# SparkFun_Main_Board_Single_v21.net
KiCad netlist of a schematic drawn in EAGLE
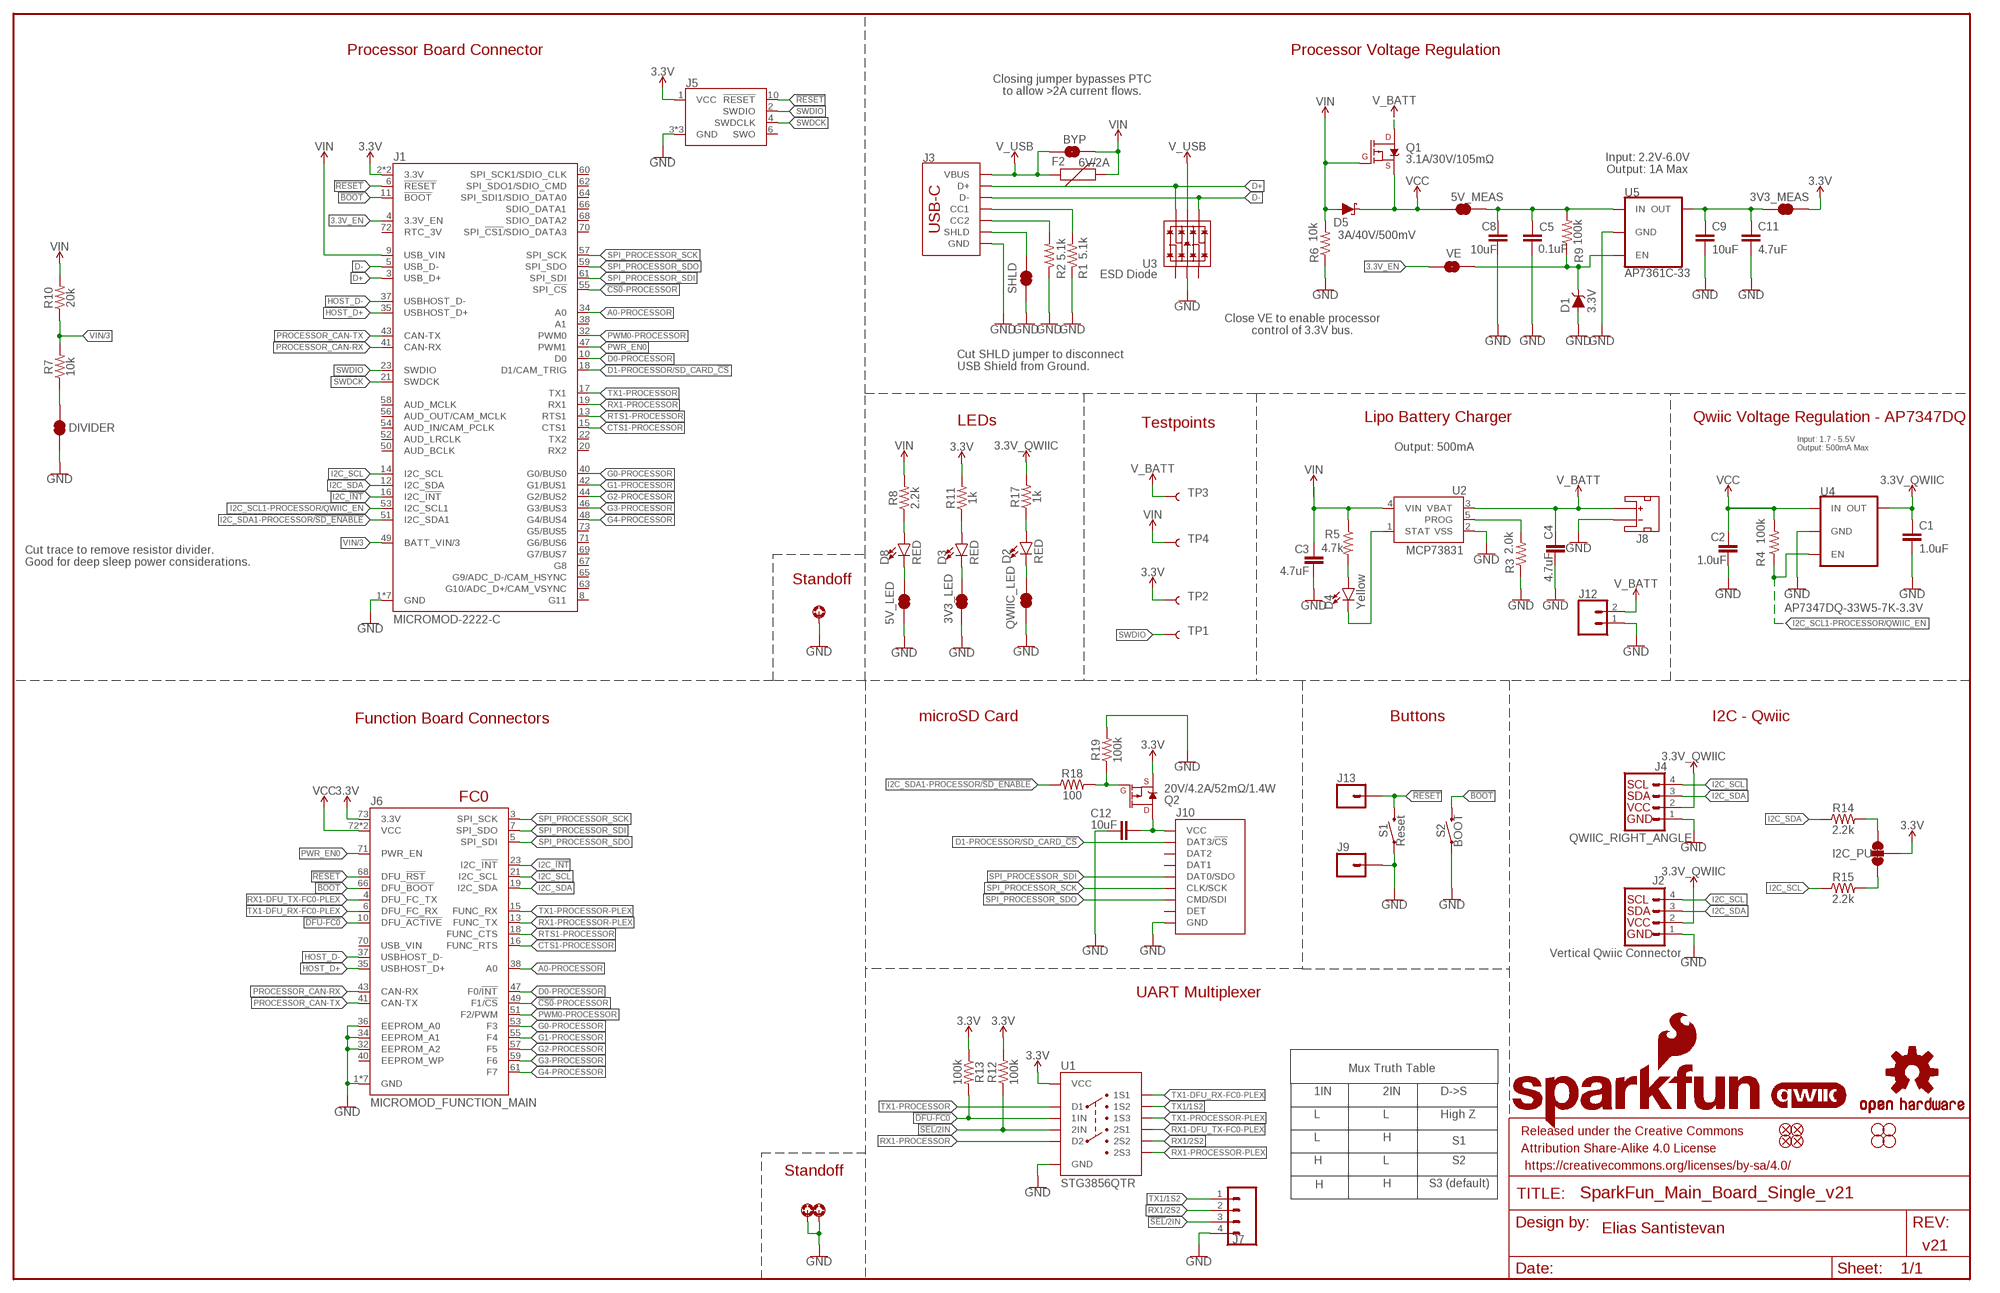
[diagram p0: schematic, sheet 1]

(export (version "E")
  (design (tool "Eeschema 10.0.6"))
  (components
    (comp (ref "3V3_LED")
      (value "JUMPER-SMT_2_NC_TRACE_SILK")
      (footprint "eagle-import:SMT-JUMPER_2_NC_TRACE_SILK")
      (libsource (lib "eagle-import") (part "JUMPER-SMT_2_NC_TRACE_SILK"))
    )
    (comp (ref "3V3_MEAS")
      (value "JUMPER-COMBO_2_NC_TRACE")
      (footprint "eagle-import:COMBO-JUMPER_2_NC_TRACE")
      (libsource (lib "eagle-import") (part "JUMPER-COMBO_2_NC_TRACE"))
    )
    (comp (ref "5V_LED")
      (value "JUMPER-SMT_2_NC_TRACE_SILK")
      (footprint "eagle-import:SMT-JUMPER_2_NC_TRACE_SILK")
      (libsource (lib "eagle-import") (part "JUMPER-SMT_2_NC_TRACE_SILK"))
    )
    (comp (ref "5V_MEAS")
      (value "JUMPER-COMBO_2_NC_TRACE")
      (footprint "eagle-import:COMBO-JUMPER_2_NC_TRACE")
      (libsource (lib "eagle-import") (part "JUMPER-COMBO_2_NC_TRACE"))
    )
    (comp (ref "BYP")
      (value "JUMPER-SMT_2_NO_SILK")
      (footprint "eagle-import:SMT-JUMPER_2_NO_SILK")
      (libsource (lib "eagle-import") (part "JUMPER-SMT_2_NO_SILK"))
    )
    (comp (ref "C1")
      (value "1.0uF")
      (footprint "eagle-import:0603")
      (libsource (lib "eagle-import") (part "1.0UF-0603-16V-10%"))
    )
    (comp (ref "C2")
      (value "1.0uF")
      (footprint "eagle-import:0603")
      (libsource (lib "eagle-import") (part "1.0UF-0603-16V-10%"))
    )
    (comp (ref "C3")
      (value "4.7uF")
      (footprint "eagle-import:0603")
      (libsource (lib "eagle-import") (part "4.7UF-0603-6.3V-(10%)"))
    )
    (comp (ref "C4")
      (value "4.7uF")
      (footprint "eagle-import:0603")
      (libsource (lib "eagle-import") (part "4.7UF-0603-35V-(20%)"))
    )
    (comp (ref "C5")
      (value "0.1uF")
      (footprint "eagle-import:0603")
      (libsource (lib "eagle-import") (part "0.1UF-0603-25V-(+80/-20%)"))
    )
    (comp (ref "C8")
      (value "10uF")
      (footprint "eagle-import:0805")
      (libsource (lib "eagle-import") (part "10UF-0805-10V-10%"))
    )
    (comp (ref "C9")
      (value "10uF")
      (footprint "eagle-import:0603")
      (libsource (lib "eagle-import") (part "10UF-0603-6.3V-20%"))
    )
    (comp (ref "C11")
      (value "4.7uF")
      (footprint "eagle-import:0603")
      (libsource (lib "eagle-import") (part "4.7UF-0603-6.3V-(10%)"))
    )
    (comp (ref "C12")
      (value "10uF")
      (footprint "eagle-import:0603")
      (libsource (lib "eagle-import") (part "10UF-0603-6.3V-20%"))
    )
    (comp (ref "D1")
      (value "3.3V")
      (footprint "eagle-import:SOD-323")
      (libsource (lib "eagle-import") (part "DIODE-ZENER-MM3Z3V3T1G"))
    )
    (comp (ref "D2")
      (value "RED")
      (footprint "eagle-import:LED-0603")
      (libsource (lib "eagle-import") (part "LED-RED0603"))
    )
    (comp (ref "D3")
      (value "RED")
      (footprint "eagle-import:LED-0603")
      (libsource (lib "eagle-import") (part "LED-RED0603"))
    )
    (comp (ref "D4")
      (value "Yellow")
      (footprint "eagle-import:LED-0603")
      (libsource (lib "eagle-import") (part "LED-YELLOW0603"))
    )
    (comp (ref "D5")
      (value "3A/40V/500mV")
      (footprint "eagle-import:SMA-DIODE")
      (libsource (lib "eagle-import") (part "DIODE-SCHOTTKY-B340A"))
    )
    (comp (ref "D8")
      (value "RED")
      (footprint "eagle-import:LED-0603")
      (libsource (lib "eagle-import") (part "LED-RED0603"))
    )
    (comp (ref "DIVIDER")
      (value "JUMPER-SMT_2_NC_TRACE_SILK")
      (footprint "eagle-import:SMT-JUMPER_2_NC_TRACE_SILK")
      (libsource (lib "eagle-import") (part "JUMPER-SMT_2_NC_TRACE_SILK"))
    )
    (comp (ref "F2")
      (value "6V/2A")
      (footprint "eagle-import:1210")
      (libsource (lib "eagle-import") (part "PPTC_6V2A"))
    )
    (comp (ref "FD1")
      (value "FIDUCIAL1X2")
      (footprint "eagle-import:FIDUCIAL-1X2")
      (libsource (lib "eagle-import") (part "FIDUCIAL1X2"))
    )
    (comp (ref "FD2")
      (value "FIDUCIAL1X2")
      (footprint "eagle-import:FIDUCIAL-1X2")
      (libsource (lib "eagle-import") (part "FIDUCIAL1X2"))
    )
    (comp (ref "FD3")
      (value "FIDUCIAL1X2")
      (footprint "eagle-import:FIDUCIAL-1X2")
      (libsource (lib "eagle-import") (part "FIDUCIAL1X2"))
    )
    (comp (ref "FD4")
      (value "FIDUCIAL1X2")
      (footprint "eagle-import:FIDUCIAL-1X2")
      (libsource (lib "eagle-import") (part "FIDUCIAL1X2"))
    )
    (comp (ref "FRAME1")
      (value "FRAME-LEDGER")
      (footprint "eagle-import:CREATIVE_COMMONS")
      (libsource (lib "eagle-import") (part "FRAME-LEDGER"))
    )
    (comp (ref "H2")
      (value "STAND-OFF-REFLOW-M2.5_2.5MM_TALL")
      (footprint "eagle-import:STAND-OFF-REFLOW-M2.5")
      (libsource (lib "eagle-import") (part "STAND-OFF-REFLOW-M2.5_2.5MM_TALL"))
    )
    (comp (ref "H4")
      (value "STAND-OFF-REFLOW-M2.5_2.5MM_TALL")
      (footprint "eagle-import:STAND-OFF-REFLOW-M2.5")
      (libsource (lib "eagle-import") (part "STAND-OFF-REFLOW-M2.5_2.5MM_TALL"))
    )
    (comp (ref "H8")
      (value "STAND-OFF-REFLOW-M2.5_2.5MM_TALL")
      (footprint "eagle-import:STAND-OFF-REFLOW-M2.5")
      (libsource (lib "eagle-import") (part "STAND-OFF-REFLOW-M2.5_2.5MM_TALL"))
    )
    (comp (ref "H14")
      (value "STAND-OFFTIGHT")
      (footprint "eagle-import:STAND-OFF-TIGHT")
      (libsource (lib "eagle-import") (part "STAND-OFFTIGHT"))
    )
    (comp (ref "H15")
      (value "STAND-OFFTIGHT")
      (footprint "eagle-import:STAND-OFF-TIGHT")
      (libsource (lib "eagle-import") (part "STAND-OFFTIGHT"))
    )
    (comp (ref "H16")
      (value "STAND-OFFTIGHT")
      (footprint "eagle-import:STAND-OFF-TIGHT")
      (libsource (lib "eagle-import") (part "STAND-OFFTIGHT"))
    )
    (comp (ref "H17")
      (value "STAND-OFFTIGHT")
      (footprint "eagle-import:STAND-OFF-TIGHT")
      (libsource (lib "eagle-import") (part "STAND-OFFTIGHT"))
    )
    (comp (ref "I2C_PU")
      (value "JUMPER-SMT_3_2-NC_TRACE_SILK")
      (footprint "eagle-import:SMT-JUMPER_3_2-NC_TRACE_SILK")
      (libsource (lib "eagle-import") (part "JUMPER-SMT_3_2-NC_TRACE_SILK"))
    )
    (comp (ref "J1")
      (value "MICROMOD-2222-C")
      (footprint "eagle-import:M.2-CONNECTOR-E")
      (libsource (lib "eagle-import") (part "MICROMOD-2222-C"))
    )
    (comp (ref "J2")
      (value "Vertical Qwiic Connector")
      (footprint "eagle-import:JST04_1MM_VERT")
      (libsource (lib "eagle-import") (part "QWIIC_CONNECTOR"))
    )
    (comp (ref "J3")
      (value "USB_C_2-LAYER_PADS")
      (footprint "eagle-import:USB-C-16P-2LAYER-PADS")
      (libsource (lib "eagle-import") (part "USB_C_2-LAYER_PADS"))
    )
    (comp (ref "J4")
      (value "QWIIC_RIGHT_ANGLE")
      (footprint "eagle-import:JST04_1MM_RA")
      (libsource (lib "eagle-import") (part "QWIIC_CONNECTORJS-1MM"))
    )
    (comp (ref "J5")
      (value "CORTEX_JTAG_DEBUG_MINIMUM_PTH")
      (footprint "eagle-import:2X5-PTH-1.27MM")
      (libsource (lib "eagle-import") (part "CORTEX_JTAG_DEBUG_MINIMUM_PTH"))
    )
    (comp (ref "J6")
      (value "MICROMOD_FUNCTION_MAIN")
      (footprint "eagle-import:M.2-CONNECTOR-E-FUNCTION-STANDARD")
      (libsource (lib "eagle-import") (part "MICROMOD_FUNCTION_MAIN"))
    )
    (comp (ref "J7")
      (value "CONN_041X04_NO_SILK")
      (footprint "eagle-import:1X04_NO_SILK")
      (libsource (lib "eagle-import") (part "CONN_041X04_NO_SILK"))
    )
    (comp (ref "J8")
      (value "JST_2MM_MALE")
      (footprint "eagle-import:JST-2-SMD")
      (libsource (lib "eagle-import") (part "JST_2MM_MALE"))
    )
    (comp (ref "J9")
      (value "CONN_01PTH_NO_SILK_YES_STOP")
      (footprint "eagle-import:1X01_NO_SILK")
      (libsource (lib "eagle-import") (part "CONN_01PTH_NO_SILK_YES_STOP"))
    )
    (comp (ref "J10")
      (value "MICRO-SD-PUSH-PUSH-EXT-PIN")
      (footprint "eagle-import:MICROSD-EXTERNALPIN")
      (libsource (lib "eagle-import") (part "MICRO-SD-PUSH-PUSH-EXT-PIN"))
    )
    (comp (ref "J12")
      (value "CONN_021X02_NO_SILK")
      (footprint "eagle-import:1X02_NO_SILK")
      (libsource (lib "eagle-import") (part "CONN_021X02_NO_SILK"))
    )
    (comp (ref "J13")
      (value "CONN_01PTH_NO_SILK_YES_STOP")
      (footprint "eagle-import:1X01_NO_SILK")
      (libsource (lib "eagle-import") (part "CONN_01PTH_NO_SILK_YES_STOP"))
    )
    (comp (ref "LOGO1")
      (value "QWIIC_LOGO_8MM")
      (footprint "eagle-import:QWIIC_8MM")
      (libsource (lib "eagle-import") (part "QWIIC_LOGO_8MM"))
    )
    (comp (ref "LOGO2")
      (value "SFE_LOGO_NAME_FLAME.3_INCH")
      (footprint "eagle-import:SFE_LOGO_NAME_FLAME_.3")
      (libsource (lib "eagle-import") (part "SFE_LOGO_NAME_FLAME.3_INCH"))
    )
    (comp (ref "LOGO3")
      (value "OSHW-LOGOL")
      (footprint "eagle-import:OSHW-LOGO-L")
      (libsource (lib "eagle-import") (part "OSHW-LOGOL"))
    )
    (comp (ref "Q1")
      (value "3.1A/30V/105mΩ")
      (footprint "eagle-import:SOT23-3")
      (libsource (lib "eagle-import") (part "MOSFET_PCH-DMG2307L"))
    )
    (comp (ref "Q2")
      (value "20V/4.2A/52mΩ/1.4W")
      (footprint "eagle-import:SOT23-3")
      (libsource (lib "eagle-import") (part "MOSFET_PCH-DMG2305UX-7"))
    )
    (comp (ref "QWIIC_LED")
      (value "JUMPER-SMT_2_NC_TRACE_SILK")
      (footprint "eagle-import:SMT-JUMPER_2_NC_TRACE_SILK")
      (libsource (lib "eagle-import") (part "JUMPER-SMT_2_NC_TRACE_SILK"))
    )
    (comp (ref "R1")
      (value "5.1k")
      (footprint "eagle-import:0603")
      (libsource (lib "eagle-import") (part "5.1KOHM5.1KOHM-0603-1/10W-1%"))
    )
    (comp (ref "R2")
      (value "5.1k")
      (footprint "eagle-import:0603")
      (libsource (lib "eagle-import") (part "5.1KOHM5.1KOHM-0603-1/10W-1%"))
    )
    (comp (ref "R3")
      (value "2.0k")
      (footprint "eagle-import:0603")
      (libsource (lib "eagle-import") (part "2.0KOHM-0603-1/10W-5%"))
    )
    (comp (ref "R4")
      (value "100k")
      (footprint "eagle-import:0603")
      (libsource (lib "eagle-import") (part "100KOHM-0603-1/10W-1%"))
    )
    (comp (ref "R5")
      (value "4.7k")
      (footprint "eagle-import:0603")
      (libsource (lib "eagle-import") (part "4.7KOHM-0603-1/10W-1%"))
    )
    (comp (ref "R6")
      (value "10k")
      (footprint "eagle-import:0603")
      (libsource (lib "eagle-import") (part "10KOHM-0603-1/10W-1%"))
    )
    (comp (ref "R7")
      (value "10k")
      (footprint "eagle-import:0603")
      (libsource (lib "eagle-import") (part "10KOHM-0603-1/10W-1%"))
    )
    (comp (ref "R8")
      (value "2.2k")
      (footprint "eagle-import:0603")
      (libsource (lib "eagle-import") (part "2.2KOHM-0603-1/10W-1%"))
    )
    (comp (ref "R9")
      (value "100k")
      (footprint "eagle-import:0603")
      (libsource (lib "eagle-import") (part "100KOHM-0603-1/10W-1%"))
    )
    (comp (ref "R10")
      (value "20k")
      (footprint "eagle-import:0603")
      (libsource (lib "eagle-import") (part "20KOHM-0603-1/10W-1%"))
    )
    (comp (ref "R11")
      (value "1k")
      (footprint "eagle-import:0603")
      (libsource (lib "eagle-import") (part "1KOHM-0603-1/10W-1%"))
    )
    (comp (ref "R12")
      (value "100k")
      (footprint "eagle-import:0603")
      (libsource (lib "eagle-import") (part "100KOHM-0603-1/10W-1%"))
    )
    (comp (ref "R13")
      (value "100k")
      (footprint "eagle-import:0603")
      (libsource (lib "eagle-import") (part "100KOHM-0603-1/10W-1%"))
    )
    (comp (ref "R14")
      (value "2.2k")
      (footprint "eagle-import:0603")
      (libsource (lib "eagle-import") (part "2.2KOHM-0603-1/10W-1%"))
    )
    (comp (ref "R15")
      (value "2.2k")
      (footprint "eagle-import:0603")
      (libsource (lib "eagle-import") (part "2.2KOHM-0603-1/10W-1%"))
    )
    (comp (ref "R17")
      (value "1k")
      (footprint "eagle-import:0603")
      (libsource (lib "eagle-import") (part "1KOHM-0603-1/10W-1%"))
    )
    (comp (ref "R18")
      (value "100")
      (footprint "eagle-import:0603")
      (libsource (lib "eagle-import") (part "100OHM-0603-1/10W-1%"))
    )
    (comp (ref "R19")
      (value "100k")
      (footprint "eagle-import:0603")
      (libsource (lib "eagle-import") (part "100KOHM-0603-1/10W-1%"))
    )
    (comp (ref "S1")
      (value "Reset")
      (footprint "eagle-import:TACTILE_SWITCH_SMD_5.2MM")
      (libsource (lib "eagle-import") (part "MOMENTARY-SWITCH-SPST-SMD-5.2-TALL-REDUNDANT"))
    )
    (comp (ref "S2")
      (value "BOOT")
      (footprint "eagle-import:TACTILE_SWITCH_SMD_5.2MM")
      (libsource (lib "eagle-import") (part "MOMENTARY-SWITCH-SPST-SMD-5.2-TALL-REDUNDANT"))
    )
    (comp (ref "SHLD")
      (value "JUMPER-SMT_2_NC_TRACE_SILK")
      (footprint "eagle-import:SMT-JUMPER_2_NC_TRACE_SILK")
      (libsource (lib "eagle-import") (part "JUMPER-SMT_2_NC_TRACE_SILK"))
    )
    (comp (ref "TP1")
      (value "TEST-POINT3X5")
      (footprint "eagle-import:PAD.03X.05")
      (libsource (lib "eagle-import") (part "TEST-POINT3X5"))
    )
    (comp (ref "TP2")
      (value "TEST-POINT3X5")
      (footprint "eagle-import:PAD.03X.05")
      (libsource (lib "eagle-import") (part "TEST-POINT3X5"))
    )
    (comp (ref "TP3")
      (value "TEST-POINT3X5")
      (footprint "eagle-import:PAD.03X.05")
      (libsource (lib "eagle-import") (part "TEST-POINT3X5"))
    )
    (comp (ref "TP4")
      (value "TEST-POINT3X5")
      (footprint "eagle-import:PAD.03X.05")
      (libsource (lib "eagle-import") (part "TEST-POINT3X5"))
    )
    (comp (ref "U1")
      (value "STG3856QTR")
      (footprint "eagle-import:STG3856")
      (libsource (lib "eagle-import") (part "STG3856QTR"))
    )
    (comp (ref "U2")
      (value "MCP73831")
      (footprint "eagle-import:SOT23-5")
      (libsource (lib "eagle-import") (part "MCP73831"))
    )
    (comp (ref "U3")
      (value "ESD Diode")
      (footprint "eagle-import:SOT-23-6")
      (libsource (lib "eagle-import") (part "TVS_DIODE_ARRAYSMD"))
    )
    (comp (ref "U4")
      (value "AP7347DQ-33W5-7K-3.3V")
      (footprint "eagle-import:SOT25")
      (libsource (lib "eagle-import") (part "AP7347DQ-33W5-7K-3.3V"))
    )
    (comp (ref "U5")
      (value "AP7361C-33")
      (footprint "eagle-import:UDFN-8")
      (libsource (lib "eagle-import") (part "AP7361C-33FGEUDFN-8"))
    )
    (comp (ref "VE")
      (value "JUMPER-SMT_2_NO_SILK")
      (footprint "eagle-import:SMT-JUMPER_2_NO_SILK")
      (libsource (lib "eagle-import") (part "JUMPER-SMT_2_NO_SILK"))
    )
  )
  (nets
    (net (code "1") (name "/D1-PROCESSOR{slash}SD_CARD_~{CS}") (class "Default")
      (node (ref "J1") (pin "18") (pinfunction "D1/CAM_TRIG_18") (pintype "bidirectional"))
      (node (ref "J10") (pin "2") (pinfunction "DAT3/~{CS}_2") (pintype "bidirectional"))
    )
    (net (code "2") (name "/I2C_SDA1-PROCESSOR{slash}~{SD_ENABLE}") (class "Default")
      (node (ref "J1") (pin "51") (pinfunction "I2C_SDA1_51") (pintype "bidirectional"))
      (node (ref "R18") (pin "1") (pinfunction "1_1") (pintype "passive"))
    )
    (net (code "3") (name "/I2C_~{INT}") (class "Default")
      (node (ref "J1") (pin "16") (pinfunction "I2C_~{INT}_16") (pintype "bidirectional"))
      (node (ref "J6") (pin "23") (pinfunction "I2C_~{INT}_23") (pintype "bidirectional"))
    )
    (net (code "4") (name "/~{BOOT}") (class "Default")
      (node (ref "J1") (pin "11") (pinfunction "~{BOOT}_11") (pintype "bidirectional"))
      (node (ref "J6") (pin "66") (pinfunction "DFU_~{BOOT}_66") (pintype "bidirectional"))
      (node (ref "S2") (pin "3") (pinfunction "2_3") (pintype "passive"))
      (node (ref "S2") (pin "4") (pinfunction "2_4") (pintype "passive"))
    )
    (net (code "5") (name "/~{CS0}-PROCESSOR") (class "Default")
      (node (ref "J1") (pin "55") (pinfunction "SPI_~{CS}_55") (pintype "bidirectional"))
      (node (ref "J6") (pin "49") (pinfunction "F1/~{CS}_49") (pintype "bidirectional"))
    )
    (net (code "6") (name "/~{DFU-FC0}") (class "Default")
      (node (ref "J6") (pin "10") (pinfunction "DFU_~{ACTIVE}_10") (pintype "bidirectional"))
      (node (ref "R13") (pin "2") (pinfunction "2_2") (pintype "passive"))
      (node (ref "U1") (pin "P12") (pinfunction "1IN_P12") (pintype "bidirectional"))
    )
    (net (code "7") (name "/~{RESET}") (class "Default")
      (node (ref "J1") (pin "6") (pinfunction "~{RESET}_6") (pintype "bidirectional"))
      (node (ref "J13") (pin "1") (pinfunction "1_1") (pintype "passive"))
      (node (ref "J5") (pin "10") (pinfunction "~{RESET}_10") (pintype "bidirectional"))
      (node (ref "J6") (pin "68") (pinfunction "DFU_~{RST}_68") (pintype "bidirectional"))
      (node (ref "S1") (pin "3") (pinfunction "2_3") (pintype "passive"))
      (node (ref "S1") (pin "4") (pinfunction "2_4") (pintype "passive"))
    )
    (net (code "8") (name "/~{SEL}{slash}2IN") (class "Default")
      (node (ref "J7") (pin "3") (pinfunction "3_3") (pintype "passive"))
      (node (ref "R12") (pin "1") (pinfunction "1_1") (pintype "passive"))
      (node (ref "U1") (pin "P10") (pinfunction "2IN_P10") (pintype "bidirectional"))
    )
    (net (code "9") (name "3.3V") (class "Default")
      (node (ref "3V3_MEAS") (pin "2") (pinfunction "2_2") (pintype "passive"))
      (node (ref "3V3_MEAS") (pin "4") (pinfunction "2_4") (pintype "passive"))
      (node (ref "I2C_PU") (pin "2") (pinfunction "2_2") (pintype "passive"))
      (node (ref "J1") (pin "2") (pinfunction "3.3V_2") (pintype "bidirectional"))
      (node (ref "J1") (pin "74") (pinfunction "3.3V_74") (pintype "bidirectional"))
      (node (ref "J5") (pin "1") (pinfunction "VCC_1") (pintype "bidirectional"))
      (node (ref "J6") (pin "73") (pinfunction "3.3V_73") (pintype "bidirectional"))
      (node (ref "Q2") (pin "2") (pinfunction "S_2") (pintype "bidirectional"))
      (node (ref "R11") (pin "2") (pinfunction "2_2") (pintype "passive"))
      (node (ref "R12") (pin "2") (pinfunction "2_2") (pintype "passive"))
      (node (ref "R13") (pin "1") (pinfunction "1_1") (pintype "passive"))
      (node (ref "TP2") (pin "1") (pinfunction "1_1") (pintype "bidirectional"))
      (node (ref "U1") (pin "P11") (pinfunction "VCC_P11") (pintype "power_in"))
    )
    (net (code "10") (name "3.3V_EN") (class "Default")
      (node (ref "J1") (pin "4") (pinfunction "3.3V_EN_4") (pintype "bidirectional"))
      (node (ref "VE") (pin "1") (pinfunction "1_1") (pintype "passive"))
    )
    (net (code "11") (name "3.3V_QWIIC") (class "Default")
      (node (ref "C1") (pin "1") (pinfunction "1_1") (pintype "passive"))
      (node (ref "J2") (pin "2") (pinfunction "2_2") (pintype "power_in"))
      (node (ref "J4") (pin "2") (pinfunction "2_2") (pintype "power_in"))
      (node (ref "R17") (pin "2") (pinfunction "2_2") (pintype "passive"))
      (node (ref "U4") (pin "5") (pinfunction "OUT_5") (pintype "passive"))
    )
    (net (code "12") (name "A0-PROCESSOR") (class "Default")
      (node (ref "J1") (pin "34") (pinfunction "A0_34") (pintype "bidirectional"))
      (node (ref "J6") (pin "38") (pinfunction "A0_38") (pintype "bidirectional"))
    )
    (net (code "13") (name "CTS1-PROCESSOR") (class "Default")
      (node (ref "J1") (pin "15") (pinfunction "CTS1_15") (pintype "bidirectional"))
      (node (ref "J6") (pin "16") (pinfunction "FUNC_RTS_16") (pintype "bidirectional"))
    )
    (net (code "14") (name "D+") (class "Default")
      (node (ref "J1") (pin "3") (pinfunction "USB_D+_3") (pintype "bidirectional"))
      (node (ref "J3") (pin "A6") (pinfunction "D+_A6") (pintype "bidirectional"))
      (node (ref "J3") (pin "B6") (pinfunction "D+_B6") (pintype "bidirectional"))
      (node (ref "U3") (pin "6") (pinfunction "IO4_6") (pintype "bidirectional"))
    )
    (net (code "15") (name "D-") (class "Default")
      (node (ref "J1") (pin "5") (pinfunction "USB_D-_5") (pintype "bidirectional"))
      (node (ref "J3") (pin "A7") (pinfunction "D-_A7") (pintype "bidirectional"))
      (node (ref "J3") (pin "B7") (pinfunction "D-_B7") (pintype "bidirectional"))
      (node (ref "U3") (pin "4") (pinfunction "IO3_4") (pintype "bidirectional"))
    )
    (net (code "16") (name "D0-PROCESSOR") (class "Default")
      (node (ref "J1") (pin "10") (pinfunction "D0_10") (pintype "bidirectional"))
      (node (ref "J6") (pin "47") (pinfunction "F0/~{INT}_47") (pintype "bidirectional"))
    )
    (net (code "17") (name "G0-PROCESSOR") (class "Default")
      (node (ref "J1") (pin "40") (pinfunction "G0/BUS0_40") (pintype "bidirectional"))
      (node (ref "J6") (pin "53") (pinfunction "F3_53") (pintype "bidirectional"))
    )
    (net (code "18") (name "G1-PROCESSOR") (class "Default")
      (node (ref "J1") (pin "42") (pinfunction "G1/BUS1_42") (pintype "bidirectional"))
      (node (ref "J6") (pin "55") (pinfunction "F4_55") (pintype "bidirectional"))
    )
    (net (code "19") (name "G2-PROCESSOR") (class "Default")
      (node (ref "J1") (pin "44") (pinfunction "G2/BUS2_44") (pintype "bidirectional"))
      (node (ref "J6") (pin "57") (pinfunction "F5_57") (pintype "bidirectional"))
    )
    (net (code "20") (name "G3-PROCESSOR") (class "Default")
      (node (ref "J1") (pin "46") (pinfunction "G3/BUS3_46") (pintype "bidirectional"))
      (node (ref "J6") (pin "59") (pinfunction "F6_59") (pintype "bidirectional"))
    )
    (net (code "21") (name "G4-PROCESSOR") (class "Default")
      (node (ref "J1") (pin "48") (pinfunction "G4/BUS4_48") (pintype "bidirectional"))
      (node (ref "J6") (pin "61") (pinfunction "F7_61") (pintype "bidirectional"))
    )
    (net (code "22") (name "GND") (class "Default")
      (node (ref "3V3_LED") (pin "1") (pinfunction "1_1") (pintype "passive"))
      (node (ref "5V_LED") (pin "1") (pinfunction "1_1") (pintype "passive"))
      (node (ref "C1") (pin "2") (pinfunction "2_2") (pintype "passive"))
      (node (ref "C11") (pin "2") (pinfunction "2_2") (pintype "passive"))
      (node (ref "C12") (pin "2") (pinfunction "2_2") (pintype "passive"))
      (node (ref "C2") (pin "2") (pinfunction "2_2") (pintype "passive"))
      (node (ref "C3") (pin "2") (pinfunction "2_2") (pintype "passive"))
      (node (ref "C4") (pin "2") (pinfunction "2_2") (pintype "passive"))
      (node (ref "C5") (pin "2") (pinfunction "2_2") (pintype "passive"))
      (node (ref "C8") (pin "2") (pinfunction "2_2") (pintype "passive"))
      (node (ref "C9") (pin "2") (pinfunction "2_2") (pintype "passive"))
      (node (ref "D1") (pin "A") (pinfunction "A_A") (pintype "passive"))
      (node (ref "DIVIDER") (pin "1") (pinfunction "1_1") (pintype "passive"))
      (node (ref "H2") (pin "1") (pinfunction "1_1") (pintype "bidirectional"))
      (node (ref "H4") (pin "1") (pinfunction "1_1") (pintype "bidirectional"))
      (node (ref "H8") (pin "1") (pinfunction "1_1") (pintype "bidirectional"))
      (node (ref "J1") (pin "1") (pinfunction "GND_1") (pintype "bidirectional"))
      (node (ref "J1") (pin "33") (pinfunction "GND_33") (pintype "bidirectional"))
      (node (ref "J1") (pin "36") (pinfunction "GND_36") (pintype "bidirectional"))
      (node (ref "J1") (pin "39") (pinfunction "GND_39") (pintype "bidirectional"))
      (node (ref "J1") (pin "45") (pinfunction "GND_45") (pintype "bidirectional"))
      (node (ref "J1") (pin "7") (pinfunction "GND_7") (pintype "bidirectional"))
      (node (ref "J1") (pin "75") (pinfunction "GND_75") (pintype "bidirectional"))
      (node (ref "J10") (pin "10") (pinfunction "GND_10") (pintype "bidirectional"))
      (node (ref "J10") (pin "11") (pinfunction "GND_11") (pintype "bidirectional"))
      (node (ref "J10") (pin "12") (pinfunction "GND_12") (pintype "bidirectional"))
      (node (ref "J10") (pin "13") (pinfunction "GND_13") (pintype "bidirectional"))
      (node (ref "J10") (pin "6") (pinfunction "GND_6") (pintype "bidirectional"))
      (node (ref "J12") (pin "1") (pinfunction "1_1") (pintype "passive"))
      (node (ref "J2") (pin "1") (pinfunction "1_1") (pintype "power_in"))
      (node (ref "J3") (pin "GND") (pinfunction "GND_GND") (pintype "bidirectional"))
      (node (ref "J3") (pin "GND2") (pinfunction "GND_GND2") (pintype "bidirectional"))
      (node (ref "J4") (pin "1") (pinfunction "1_1") (pintype "power_in"))
      (node (ref "J5") (pin "3") (pinfunction "GND_3") (pintype "bidirectional"))
      (node (ref "J5") (pin "5") (pinfunction "GND_5") (pintype "bidirectional"))
      (node (ref "J5") (pin "9") (pinfunction "GND_9") (pintype "bidirectional"))
      (node (ref "J6") (pin "1") (pinfunction "GND_1") (pintype "bidirectional"))
      (node (ref "J6") (pin "2") (pinfunction "GND_2") (pintype "bidirectional"))
      (node (ref "J6") (pin "32") (pinfunction "EEPROM_A2_32") (pintype "bidirectional"))
      (node (ref "J6") (pin "33") (pinfunction "GND_33") (pintype "bidirectional"))
      (node (ref "J6") (pin "34") (pinfunction "EEPROM_A1_34") (pintype "bidirectional"))
      (node (ref "J6") (pin "36") (pinfunction "EEPROM_A0_36") (pintype "bidirectional"))
      (node (ref "J6") (pin "39") (pinfunction "GND_39") (pintype "bidirectional"))
      (node (ref "J6") (pin "45") (pinfunction "GND_45") (pintype "bidirectional"))
      (node (ref "J6") (pin "75") (pinfunction "GND_75") (pintype "bidirectional"))
      (node (ref "J6") (pin "8") (pinfunction "GND_8") (pintype "bidirectional"))
      (node (ref "J7") (pin "4") (pinfunction "4_4") (pintype "passive"))
      (node (ref "J8") (pin "1") (pinfunction "-_1") (pintype "bidirectional"))
      (node (ref "J9") (pin "1") (pinfunction "1_1") (pintype "passive"))
      (node (ref "QWIIC_LED") (pin "1") (pinfunction "1_1") (pintype "passive"))
      (node (ref "R1") (pin "1") (pinfunction "1_1") (pintype "passive"))
      (node (ref "R19") (pin "2") (pinfunction "2_2") (pintype "passive"))
      (node (ref "R2") (pin "1") (pinfunction "1_1") (pintype "passive"))
      (node (ref "R3") (pin "1") (pinfunction "1_1") (pintype "passive"))
      (node (ref "R6") (pin "1") (pinfunction "1_1") (pintype "passive"))
      (node (ref "S1") (pin "1") (pinfunction "1_1") (pintype "passive"))
      (node (ref "S1") (pin "2") (pinfunction "1_2") (pintype "passive"))
      (node (ref "S2") (pin "1") (pinfunction "1_1") (pintype "passive"))
      (node (ref "S2") (pin "2") (pinfunction "1_2") (pintype "passive"))
      (node (ref "SHLD") (pin "1") (pinfunction "1_1") (pintype "passive"))
      (node (ref "U1") (pin "P5") (pinfunction "GND_P5") (pintype "power_in"))
      (node (ref "U2") (pin "2") (pinfunction "VSS_2") (pintype "power_in"))
      (node (ref "U3") (pin "2") (pinfunction "VSS_2") (pintype "bidirectional"))
      (node (ref "U4") (pin "2") (pinfunction "GND_2") (pintype "input"))
      (node (ref "U5") (pin "4") (pinfunction "GND_4") (pintype "input"))
      (node (ref "U5") (pin "EP") (pinfunction "GND_EP") (pintype "input"))
    )
    (net (code "23") (name "HOST_D+") (class "Default")
      (node (ref "J1") (pin "35") (pinfunction "USBHOST_D+_35") (pintype "bidirectional"))
      (node (ref "J6") (pin "35") (pinfunction "USBHOST_D+_35") (pintype "bidirectional"))
    )
    (net (code "24") (name "HOST_D-") (class "Default")
      (node (ref "J1") (pin "37") (pinfunction "USBHOST_D-_37") (pintype "bidirectional"))
      (node (ref "J6") (pin "37") (pinfunction "USBHOST_D-_37") (pintype "bidirectional"))
    )
    (net (code "25") (name "I2C_SCL") (class "Default")
      (node (ref "J1") (pin "14") (pinfunction "I2C_SCL_14") (pintype "bidirectional"))
      (node (ref "J2") (pin "4") (pinfunction "4_4") (pintype "passive"))
      (node (ref "J4") (pin "4") (pinfunction "4_4") (pintype "passive"))
      (node (ref "J6") (pin "21") (pinfunction "I2C_SCL_21") (pintype "bidirectional"))
      (node (ref "R15") (pin "1") (pinfunction "1_1") (pintype "passive"))
    )
    (net (code "26") (name "I2C_SCL1-PROCESSOR{slash}QWIIC_EN") (class "Default")
      (node (ref "J1") (pin "53") (pinfunction "I2C_SCL1_53") (pintype "bidirectional"))
      (node (ref "R4") (pin "1") (pinfunction "1_1") (pintype "passive"))
      (node (ref "U4") (pin "3") (pinfunction "EN_3") (pintype "input"))
    )
    (net (code "27") (name "I2C_SDA") (class "Default")
      (node (ref "J1") (pin "12") (pinfunction "I2C_SDA_12") (pintype "bidirectional"))
      (node (ref "J2") (pin "3") (pinfunction "3_3") (pintype "passive"))
      (node (ref "J4") (pin "3") (pinfunction "3_3") (pintype "passive"))
      (node (ref "J6") (pin "19") (pinfunction "I2C_SDA_19") (pintype "bidirectional"))
      (node (ref "R14") (pin "1") (pinfunction "1_1") (pintype "passive"))
    )
    (net (code "28") (name "Net-(3V3_LED-Pad2)") (class "Default")
      (node (ref "3V3_LED") (pin "2") (pinfunction "2_2") (pintype "passive"))
      (node (ref "D3") (pin "C") (pinfunction "C_C") (pintype "passive"))
    )
    (net (code "29") (name "Net-(5V_LED-Pad2)") (class "Default")
      (node (ref "5V_LED") (pin "2") (pinfunction "2_2") (pintype "passive"))
      (node (ref "D8") (pin "C") (pinfunction "C_C") (pintype "passive"))
    )
    (net (code "30") (name "Net-(D2-PadA)") (class "Default")
      (node (ref "D2") (pin "A") (pinfunction "A_A") (pintype "passive"))
      (node (ref "R17") (pin "1") (pinfunction "1_1") (pintype "passive"))
    )
    (net (code "31") (name "Net-(D2-PadC)") (class "Default")
      (node (ref "D2") (pin "C") (pinfunction "C_C") (pintype "passive"))
      (node (ref "QWIIC_LED") (pin "2") (pinfunction "2_2") (pintype "passive"))
    )
    (net (code "32") (name "Net-(D3-PadA)") (class "Default")
      (node (ref "D3") (pin "A") (pinfunction "A_A") (pintype "passive"))
      (node (ref "R11") (pin "1") (pinfunction "1_1") (pintype "passive"))
    )
    (net (code "33") (name "Net-(D4-PadA)") (class "Default")
      (node (ref "D4") (pin "A") (pinfunction "A_A") (pintype "passive"))
      (node (ref "R5") (pin "2") (pinfunction "2_2") (pintype "passive"))
    )
    (net (code "34") (name "Net-(D8-PadA)") (class "Default")
      (node (ref "D8") (pin "A") (pinfunction "A_A") (pintype "passive"))
      (node (ref "R8") (pin "1") (pinfunction "1_1") (pintype "passive"))
    )
    (net (code "35") (name "Net-(DIVIDER-Pad2)") (class "Default")
      (node (ref "DIVIDER") (pin "2") (pinfunction "2_2") (pintype "passive"))
      (node (ref "R7") (pin "1") (pinfunction "1_1") (pintype "passive"))
    )
    (net (code "36") (name "Net-(I2C_PU-Pad1)") (class "Default")
      (node (ref "I2C_PU") (pin "1") (pinfunction "1_1") (pintype "passive"))
      (node (ref "R15") (pin "2") (pinfunction "2_2") (pintype "passive"))
    )
    (net (code "37") (name "Net-(I2C_PU-Pad3)") (class "Default")
      (node (ref "I2C_PU") (pin "3") (pinfunction "3_3") (pintype "passive"))
      (node (ref "R14") (pin "2") (pinfunction "2_2") (pintype "passive"))
    )
    (net (code "38") (name "Net-(J3-CC1)") (class "Default")
      (node (ref "J3") (pin "A5") (pinfunction "CC1_A5") (pintype "bidirectional"))
      (node (ref "R1") (pin "2") (pinfunction "2_2") (pintype "passive"))
    )
    (net (code "39") (name "Net-(J3-CC2)") (class "Default")
      (node (ref "J3") (pin "B5") (pinfunction "CC2_B5") (pintype "bidirectional"))
      (node (ref "R2") (pin "2") (pinfunction "2_2") (pintype "passive"))
    )
    (net (code "40") (name "Net-(J3-SHLD-PadSHLD1)") (class "Default")
      (node (ref "J3") (pin "SHLD1") (pinfunction "SHLD_SHLD1") (pintype "bidirectional"))
      (node (ref "J3") (pin "SHLD2") (pinfunction "SHLD_SHLD2") (pintype "bidirectional"))
      (node (ref "J3") (pin "SHLD3") (pinfunction "SHLD_SHLD3") (pintype "bidirectional"))
      (node (ref "J3") (pin "SHLD4") (pinfunction "SHLD_SHLD4") (pintype "bidirectional"))
      (node (ref "SHLD") (pin "2") (pinfunction "2_2") (pintype "passive"))
    )
    (net (code "41") (name "Net-(J10-VCC)") (class "Default")
      (node (ref "C12") (pin "1") (pinfunction "1_1") (pintype "passive"))
      (node (ref "J10") (pin "4") (pinfunction "VCC_4") (pintype "bidirectional"))
      (node (ref "Q2") (pin "3") (pinfunction "D_3") (pintype "bidirectional"))
    )
    (net (code "42") (name "Net-(Q2-G)") (class "Default")
      (node (ref "Q2") (pin "1") (pinfunction "G_1") (pintype "bidirectional"))
      (node (ref "R18") (pin "2") (pinfunction "2_2") (pintype "passive"))
      (node (ref "R19") (pin "1") (pinfunction "1_1") (pintype "passive"))
    )
    (net (code "43") (name "Net-(U2-PROG)") (class "Default")
      (node (ref "R3") (pin "2") (pinfunction "2_2") (pintype "passive"))
      (node (ref "U2") (pin "5") (pinfunction "PROG_5") (pintype "input"))
    )
    (net (code "44") (name "Net-(U2-STAT)") (class "Default")
      (node (ref "D4") (pin "C") (pinfunction "C_C") (pintype "passive"))
      (node (ref "U2") (pin "1") (pinfunction "STAT_1") (pintype "output"))
    )
    (net (code "45") (name "Net-(U5-EN)") (class "Default")
      (node (ref "D1") (pin "C") (pinfunction "C_C") (pintype "passive"))
      (node (ref "R9") (pin "1") (pinfunction "1_1") (pintype "passive"))
      (node (ref "U5") (pin "5") (pinfunction "EN_5") (pintype "bidirectional"))
      (node (ref "VE") (pin "2") (pinfunction "2_2") (pintype "passive"))
    )
    (net (code "46") (name "Net-(U5-IN)") (class "Default")
      (node (ref "5V_MEAS") (pin "2") (pinfunction "2_2") (pintype "passive"))
      (node (ref "5V_MEAS") (pin "4") (pinfunction "2_4") (pintype "passive"))
      (node (ref "C5") (pin "1") (pinfunction "1_1") (pintype "passive"))
      (node (ref "C8") (pin "1") (pinfunction "1_1") (pintype "passive"))
      (node (ref "R9") (pin "2") (pinfunction "2_2") (pintype "passive"))
      (node (ref "U5") (pin "8") (pinfunction "IN_8") (pintype "input"))
    )
    (net (code "47") (name "Net-(U5-OUT)") (class "Default")
      (node (ref "3V3_MEAS") (pin "1") (pinfunction "1_1") (pintype "passive"))
      (node (ref "3V3_MEAS") (pin "3") (pinfunction "1_3") (pintype "passive"))
      (node (ref "C11") (pin "1") (pinfunction "1_1") (pintype "passive"))
      (node (ref "C9") (pin "1") (pinfunction "1_1") (pintype "passive"))
      (node (ref "U5") (pin "1") (pinfunction "OUT_1") (pintype "output"))
    )
    (net (code "48") (name "PROCESSOR_CAN-RX") (class "Default")
      (node (ref "J1") (pin "41") (pinfunction "CAN-RX_41") (pintype "bidirectional"))
      (node (ref "J6") (pin "43") (pinfunction "CAN-RX_43") (pintype "bidirectional"))
    )
    (net (code "49") (name "PROCESSOR_CAN-TX") (class "Default")
      (node (ref "J1") (pin "43") (pinfunction "CAN-TX_43") (pintype "bidirectional"))
      (node (ref "J6") (pin "41") (pinfunction "CAN-TX_41") (pintype "bidirectional"))
    )
    (net (code "50") (name "PWM0-PROCESSOR") (class "Default")
      (node (ref "J1") (pin "32") (pinfunction "PWM0_32") (pintype "bidirectional"))
      (node (ref "J6") (pin "51") (pinfunction "F2/PWM_51") (pintype "bidirectional"))
    )
    (net (code "51") (name "PWR_EN0") (class "Default")
      (node (ref "J1") (pin "47") (pinfunction "PWM1_47") (pintype "bidirectional"))
      (node (ref "J6") (pin "71") (pinfunction "PWR_EN_71") (pintype "bidirectional"))
    )
    (net (code "52") (name "RTS1-PROCESSOR") (class "Default")
      (node (ref "J1") (pin "13") (pinfunction "RTS1_13") (pintype "bidirectional"))
      (node (ref "J6") (pin "18") (pinfunction "FUNC_CTS_18") (pintype "bidirectional"))
    )
    (net (code "53") (name "RX1-DFU_TX-FC0-PLEX") (class "Default")
      (node (ref "J6") (pin "4") (pinfunction "DFU_FC_TX_4") (pintype "bidirectional"))
      (node (ref "U1") (pin "P9") (pinfunction "2S1_P9") (pintype "bidirectional"))
    )
    (net (code "54") (name "RX1-PROCESSOR") (class "Default")
      (node (ref "J1") (pin "19") (pinfunction "RX1_19") (pintype "bidirectional"))
      (node (ref "U1") (pin "P6") (pinfunction "D2_P6") (pintype "bidirectional"))
    )
    (net (code "55") (name "RX1-PROCESSOR-PLEX") (class "Default")
      (node (ref "J6") (pin "13") (pinfunction "FUNC_TX_13") (pintype "bidirectional"))
      (node (ref "U1") (pin "P7") (pinfunction "2S3_P7") (pintype "bidirectional"))
    )
    (net (code "56") (name "RX1{slash}2S2") (class "Default")
      (node (ref "J7") (pin "2") (pinfunction "2_2") (pintype "passive"))
      (node (ref "U1") (pin "P8") (pinfunction "2S2_P8") (pintype "bidirectional"))
    )
    (net (code "57") (name "SPI_PROCESSOR_SCK") (class "Default")
      (node (ref "J1") (pin "57") (pinfunction "SPI_SCK_57") (pintype "bidirectional"))
      (node (ref "J10") (pin "5") (pinfunction "CLK/SCK_5") (pintype "bidirectional"))
      (node (ref "J6") (pin "3") (pinfunction "SPI_SCK_3") (pintype "bidirectional"))
    )
    (net (code "58") (name "SPI_PROCESSOR_SDI") (class "Default")
      (node (ref "J1") (pin "61") (pinfunction "SPI_SDI_61") (pintype "bidirectional"))
      (node (ref "J10") (pin "7") (pinfunction "DAT0/SDO_7") (pintype "bidirectional"))
      (node (ref "J6") (pin "7") (pinfunction "SPI_SDO_7") (pintype "bidirectional"))
    )
    (net (code "59") (name "SPI_PROCESSOR_SDO") (class "Default")
      (node (ref "J1") (pin "59") (pinfunction "SPI_SDO_59") (pintype "bidirectional"))
      (node (ref "J10") (pin "3") (pinfunction "CMD/SDI_3") (pintype "bidirectional"))
      (node (ref "J6") (pin "5") (pinfunction "SPI_SDI_5") (pintype "bidirectional"))
    )
    (net (code "60") (name "SWDCK") (class "Default")
      (node (ref "J1") (pin "21") (pinfunction "SWDCK_21") (pintype "bidirectional"))
      (node (ref "J5") (pin "4") (pinfunction "SWDCLK_4") (pintype "bidirectional"))
    )
    (net (code "61") (name "SWDIO") (class "Default")
      (node (ref "J1") (pin "23") (pinfunction "SWDIO_23") (pintype "bidirectional"))
      (node (ref "J5") (pin "2") (pinfunction "SWDIO_2") (pintype "bidirectional"))
      (node (ref "TP1") (pin "1") (pinfunction "1_1") (pintype "bidirectional"))
    )
    (net (code "62") (name "TX1-DFU_RX-FC0-PLEX") (class "Default")
      (node (ref "J6") (pin "6") (pinfunction "DFU_FC_RX_6") (pintype "bidirectional"))
      (node (ref "U1") (pin "P1") (pinfunction "1S1_P1") (pintype "bidirectional"))
    )
    (net (code "63") (name "TX1-PROCESSOR") (class "Default")
      (node (ref "J1") (pin "17") (pinfunction "TX1_17") (pintype "bidirectional"))
      (node (ref "U1") (pin "P4") (pinfunction "D1_P4") (pintype "bidirectional"))
    )
    (net (code "64") (name "TX1-PROCESSOR-PLEX") (class "Default")
      (node (ref "J6") (pin "15") (pinfunction "FUNC_RX_15") (pintype "bidirectional"))
      (node (ref "U1") (pin "P3") (pinfunction "1S3_P3") (pintype "bidirectional"))
    )
    (net (code "65") (name "TX1{slash}1S2") (class "Default")
      (node (ref "J7") (pin "1") (pinfunction "1_1") (pintype "passive"))
      (node (ref "U1") (pin "P2") (pinfunction "1S2_P2") (pintype "bidirectional"))
    )
    (net (code "66") (name "VCC") (class "Default")
      (node (ref "5V_MEAS") (pin "1") (pinfunction "1_1") (pintype "passive"))
      (node (ref "5V_MEAS") (pin "3") (pinfunction "1_3") (pintype "passive"))
      (node (ref "C2") (pin "1") (pinfunction "1_1") (pintype "passive"))
      (node (ref "D5") (pin "C") (pinfunction "C_C") (pintype "passive"))
      (node (ref "J6") (pin "72") (pinfunction "VCC_72") (pintype "bidirectional"))
      (node (ref "J6") (pin "74") (pinfunction "VCC_74") (pintype "bidirectional"))
      (node (ref "Q1") (pin "2") (pinfunction "S_2") (pintype "bidirectional"))
      (node (ref "R4") (pin "2") (pinfunction "2_2") (pintype "passive"))
      (node (ref "U4") (pin "1") (pinfunction "IN_1") (pintype "input"))
    )
    (net (code "67") (name "VIN") (class "Default")
      (node (ref "BYP") (pin "2") (pinfunction "2_2") (pintype "passive"))
      (node (ref "C3") (pin "1") (pinfunction "1_1") (pintype "passive"))
      (node (ref "D5") (pin "A") (pinfunction "A_A") (pintype "passive"))
      (node (ref "F2") (pin "2") (pinfunction "2_2") (pintype "bidirectional"))
      (node (ref "J1") (pin "9") (pinfunction "USB_VIN_9") (pintype "bidirectional"))
      (node (ref "Q1") (pin "1") (pinfunction "G_1") (pintype "bidirectional"))
      (node (ref "R10") (pin "2") (pinfunction "2_2") (pintype "passive"))
      (node (ref "R5") (pin "1") (pinfunction "1_1") (pintype "passive"))
      (node (ref "R6") (pin "2") (pinfunction "2_2") (pintype "passive"))
      (node (ref "R8") (pin "2") (pinfunction "2_2") (pintype "passive"))
      (node (ref "TP4") (pin "1") (pinfunction "1_1") (pintype "bidirectional"))
      (node (ref "U2") (pin "4") (pinfunction "VIN_4") (pintype "power_in"))
    )
    (net (code "68") (name "VIN{slash}3") (class "Default")
      (node (ref "J1") (pin "49") (pinfunction "BATT_VIN/3_49") (pintype "bidirectional"))
      (node (ref "R10") (pin "1") (pinfunction "1_1") (pintype "passive"))
      (node (ref "R7") (pin "2") (pinfunction "2_2") (pintype "passive"))
    )
    (net (code "69") (name "V_BATT") (class "Default")
      (node (ref "C4") (pin "1") (pinfunction "1_1") (pintype "passive"))
      (node (ref "J12") (pin "2") (pinfunction "2_2") (pintype "passive"))
      (node (ref "J8") (pin "2") (pinfunction "+_2") (pintype "bidirectional"))
      (node (ref "Q1") (pin "3") (pinfunction "D_3") (pintype "bidirectional"))
      (node (ref "TP3") (pin "1") (pinfunction "1_1") (pintype "bidirectional"))
      (node (ref "U2") (pin "3") (pinfunction "VBAT_3") (pintype "power_in"))
    )
    (net (code "70") (name "V_USB") (class "Default")
      (node (ref "BYP") (pin "1") (pinfunction "1_1") (pintype "passive"))
      (node (ref "F2") (pin "1") (pinfunction "1_1") (pintype "bidirectional"))
      (node (ref "J3") (pin "VBUS1") (pinfunction "VBUS_VBUS1") (pintype "bidirectional"))
      (node (ref "J3") (pin "VBUS2") (pinfunction "VBUS_VBUS2") (pintype "bidirectional"))
      (node (ref "U3") (pin "5") (pinfunction "VCC_5") (pintype "bidirectional"))
    )
    (net (code "71") (name "unconnected-(J1-A1-Pad38)") (class "Default")
      (node (ref "J1") (pin "38") (pinfunction "A1_38") (pintype "bidirectional"))
    )
    (net (code "72") (name "unconnected-(J1-AUD_BCLK-Pad50)") (class "Default")
      (node (ref "J1") (pin "50") (pinfunction "AUD_BCLK_50") (pintype "bidirectional"))
    )
    (net (code "73") (name "unconnected-(J1-AUD_IN{slash}CAM_PCLK-Pad54)") (class "Default")
      (node (ref "J1") (pin "54") (pinfunction "AUD_IN/CAM_PCLK_54") (pintype "bidirectional"))
    )
    (net (code "74") (name "unconnected-(J1-AUD_LRCLK-Pad52)") (class "Default")
      (node (ref "J1") (pin "52") (pinfunction "AUD_LRCLK_52") (pintype "bidirectional"))
    )
    (net (code "75") (name "unconnected-(J1-AUD_MCLK-Pad58)") (class "Default")
      (node (ref "J1") (pin "58") (pinfunction "AUD_MCLK_58") (pintype "bidirectional"))
    )
    (net (code "76") (name "unconnected-(J1-AUD_OUT{slash}CAM_MCLK-Pad56)") (class "Default")
      (node (ref "J1") (pin "56") (pinfunction "AUD_OUT/CAM_MCLK_56") (pintype "bidirectional"))
    )
    (net (code "77") (name "unconnected-(J1-G5{slash}BUS5-Pad73)") (class "Default")
      (node (ref "J1") (pin "73") (pinfunction "G5/BUS5_73") (pintype "bidirectional"))
    )
    (net (code "78") (name "unconnected-(J1-G6{slash}BUS6-Pad71)") (class "Default")
      (node (ref "J1") (pin "71") (pinfunction "G6/BUS6_71") (pintype "bidirectional"))
    )
    (net (code "79") (name "unconnected-(J1-G7{slash}BUS7-Pad69)") (class "Default")
      (node (ref "J1") (pin "69") (pinfunction "G7/BUS7_69") (pintype "bidirectional"))
    )
    (net (code "80") (name "unconnected-(J1-G8-Pad67)") (class "Default")
      (node (ref "J1") (pin "67") (pinfunction "G8_67") (pintype "bidirectional"))
    )
    (net (code "81") (name "unconnected-(J1-G9{slash}ADC_D-{slash}CAM_HSYNC-Pad65)") (class "Default")
      (node (ref "J1") (pin "65") (pinfunction "G9/ADC_D-/CAM_HSYNC_65") (pintype "bidirectional"))
    )
    (net (code "82") (name "unconnected-(J1-G10{slash}ADC_D+{slash}CAM_VSYNC-Pad63)") (class "Default")
      (node (ref "J1") (pin "63") (pinfunction "G10/ADC_D+/CAM_VSYNC_63") (pintype "bidirectional"))
    )
    (net (code "83") (name "unconnected-(J1-G11-Pad8)") (class "Default")
      (node (ref "J1") (pin "8") (pinfunction "G11_8") (pintype "bidirectional"))
    )
    (net (code "84") (name "unconnected-(J1-RTC_3V-Pad72)") (class "Default")
      (node (ref "J1") (pin "72") (pinfunction "RTC_3V_72") (pintype "bidirectional"))
    )
    (net (code "85") (name "unconnected-(J1-RX2-Pad20)") (class "Default")
      (node (ref "J1") (pin "20") (pinfunction "RX2_20") (pintype "bidirectional"))
    )
    (net (code "86") (name "unconnected-(J1-SDIO_DATA1-Pad66)") (class "Default")
      (node (ref "J1") (pin "66") (pinfunction "SDIO_DATA1_66") (pintype "bidirectional"))
    )
    (net (code "87") (name "unconnected-(J1-SDIO_DATA2-Pad68)") (class "Default")
      (node (ref "J1") (pin "68") (pinfunction "SDIO_DATA2_68") (pintype "bidirectional"))
    )
    (net (code "88") (name "unconnected-(J1-SPI_SCK1{slash}SDIO_CLK-Pad60)") (class "Default")
      (node (ref "J1") (pin "60") (pinfunction "SPI_SCK1/SDIO_CLK_60") (pintype "bidirectional"))
    )
    (net (code "89") (name "unconnected-(J1-SPI_SDI1{slash}SDIO_DATA0-Pad64)") (class "Default")
      (node (ref "J1") (pin "64") (pinfunction "SPI_SDI1/SDIO_DATA0_64") (pintype "bidirectional"))
    )
    (net (code "90") (name "unconnected-(J1-SPI_SDO1{slash}SDIO_CMD-Pad62)") (class "Default")
      (node (ref "J1") (pin "62") (pinfunction "SPI_SDO1/SDIO_CMD_62") (pintype "bidirectional"))
    )
    (net (code "91") (name "unconnected-(J1-SPI_~{CS1}{slash}SDIO_DATA3-Pad70)") (class "Default")
      (node (ref "J1") (pin "70") (pinfunction "SPI_~{CS1}/SDIO_DATA3_70") (pintype "bidirectional"))
    )
    (net (code "92") (name "unconnected-(J1-TX2-Pad22)") (class "Default")
      (node (ref "J1") (pin "22") (pinfunction "TX2_22") (pintype "bidirectional"))
    )
    (net (code "93") (name "unconnected-(J5-SWO-Pad6)") (class "Default")
      (node (ref "J5") (pin "6") (pinfunction "SWO_6") (pintype "bidirectional"))
    )
    (net (code "94") (name "unconnected-(J6-EEPROM_WP-Pad40)") (class "Default")
      (node (ref "J6") (pin "40") (pinfunction "EEPROM_WP_40") (pintype "bidirectional"))
    )
    (net (code "95") (name "unconnected-(J6-USB_VIN-Pad70)") (class "Default")
      (node (ref "J6") (pin "70") (pinfunction "USB_VIN_70") (pintype "bidirectional"))
    )
    (net (code "96") (name "unconnected-(J8-PAD1-PadNC1)") (class "Default")
      (node (ref "J8") (pin "NC1") (pinfunction "PAD1_NC1") (pintype "bidirectional"))
    )
    (net (code "97") (name "unconnected-(J8-PAD2-PadNC2)") (class "Default")
      (node (ref "J8") (pin "NC2") (pinfunction "PAD2_NC2") (pintype "bidirectional"))
    )
    (net (code "98") (name "unconnected-(J10-DAT1-Pad8)") (class "Default")
      (node (ref "J10") (pin "8") (pinfunction "DAT1_8") (pintype "bidirectional"))
    )
    (net (code "99") (name "unconnected-(J10-DAT2-Pad1)") (class "Default")
      (node (ref "J10") (pin "1") (pinfunction "DAT2_1") (pintype "bidirectional"))
    )
    (net (code "100") (name "unconnected-(J10-DET-Pad9)") (class "Default")
      (node (ref "J10") (pin "9") (pinfunction "DET_9") (pintype "bidirectional"))
    )
    (net (code "101") (name "unconnected-(U3-IO1-Pad1)") (class "Default")
      (node (ref "U3") (pin "1") (pinfunction "IO1_1") (pintype "bidirectional"))
    )
    (net (code "102") (name "unconnected-(U3-IO2-Pad3)") (class "Default")
      (node (ref "U3") (pin "3") (pinfunction "IO2_3") (pintype "bidirectional"))
    )
  )
)
